# GateWay.net
KiCad netlist of a schematic drawn in Altium Designer
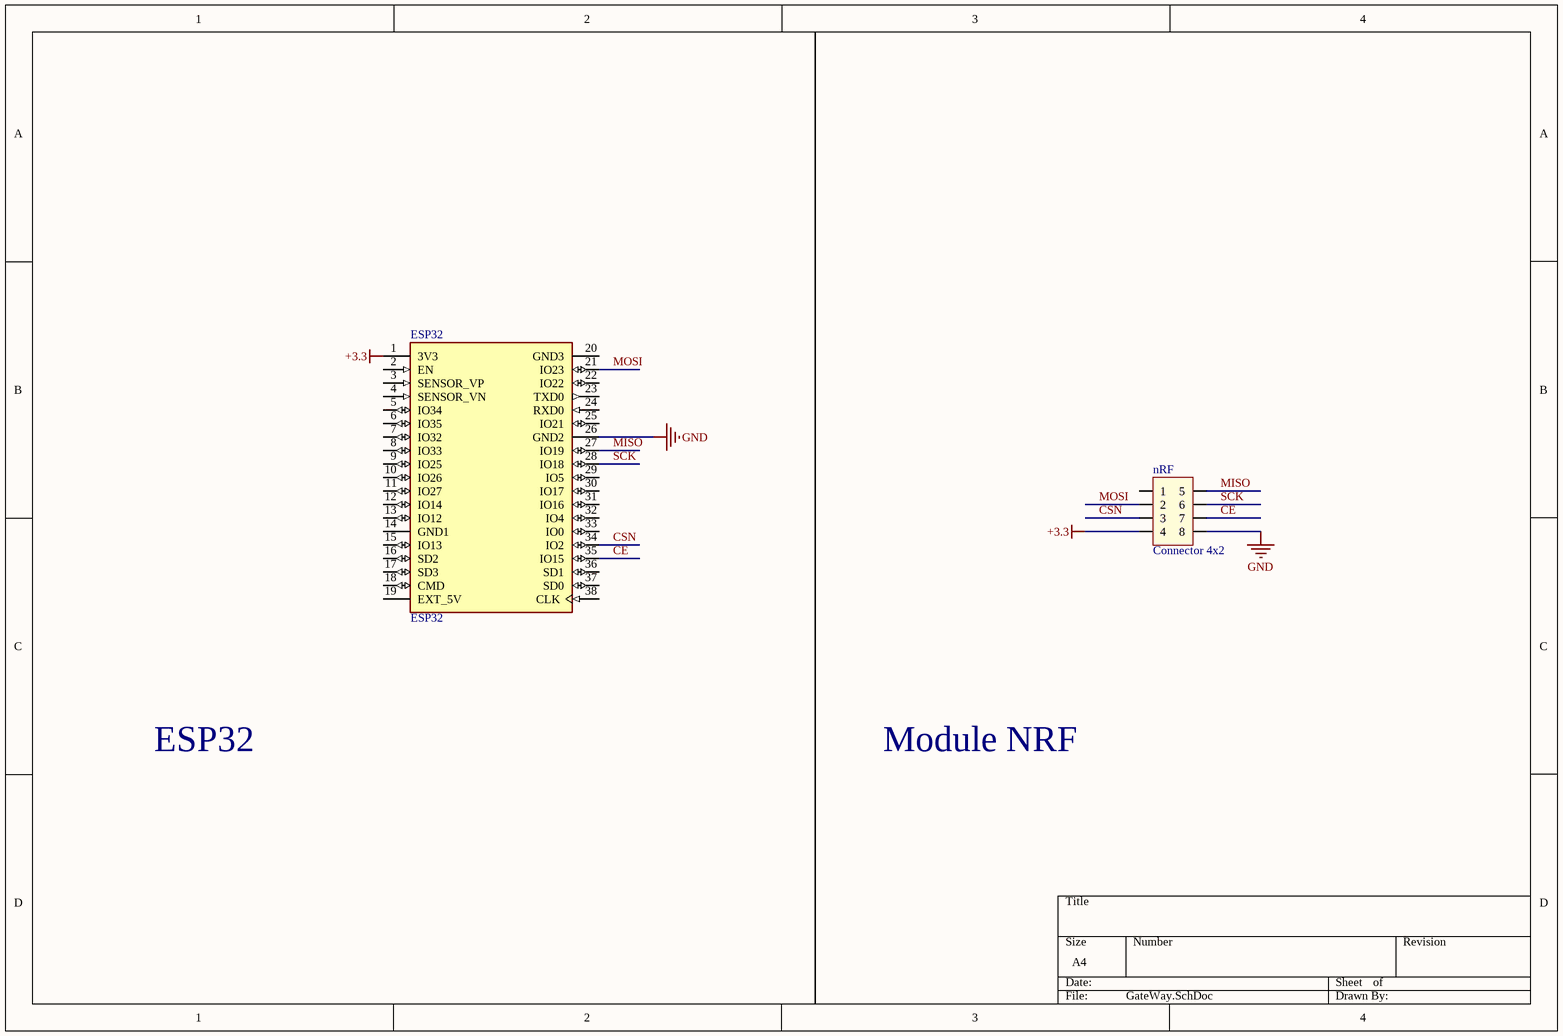
[diagram p0: GateWay.SchDoc]

(export (version "E")
  (design (tool "Eeschema 10.0.6"))
  (components
    (comp (ref "ESP32")
      (value "ESP32")
      (footprint "MODULE_ESP32-DEVKITC-32D")
      (description "EVAL BOARD FOR ESP-WROOM-32")
      (fields (field (name "MP") "ESP32-DEVKITC-32D") (field (name "MF") "Espressif Systems"))
      (libsource (lib "ESP32-DEVKITC-32D") (part "ESP32-DEVKITC-32D"))
    )
    (comp (ref "nRF")
      (value "Connector 4x2")
      (footprint "JP4x2")
      (libsource (lib "syhaunguyen__1") (part "JP4x2"))
    )
  )
  (nets
    (net (code "1") (name "+3.3") (class "Default")
      (node (ref "ESP32") (pin "1") (pinfunction "3V3_1") (pintype "power_in"))
      (node (ref "nRF") (pin "4") (pinfunction "4_4") (pintype "passive"))
    )
    (net (code "2") (name "/CE") (class "Default")
      (node (ref "ESP32") (pin "35") (pinfunction "IO15_35") (pintype "bidirectional"))
      (node (ref "nRF") (pin "7") (pinfunction "7_7") (pintype "passive"))
    )
    (net (code "3") (name "/CSN") (class "Default")
      (node (ref "ESP32") (pin "34") (pinfunction "IO2_34") (pintype "bidirectional"))
      (node (ref "nRF") (pin "3") (pinfunction "3_3") (pintype "passive"))
    )
    (net (code "4") (name "/MISO") (class "Default")
      (node (ref "ESP32") (pin "27") (pinfunction "IO19_27") (pintype "bidirectional"))
      (node (ref "nRF") (pin "5") (pinfunction "5_5") (pintype "passive"))
    )
    (net (code "5") (name "/MOSI") (class "Default")
      (node (ref "ESP32") (pin "21") (pinfunction "IO23_21") (pintype "bidirectional"))
      (node (ref "nRF") (pin "2") (pinfunction "2_2") (pintype "passive"))
    )
    (net (code "6") (name "/SCK") (class "Default")
      (node (ref "ESP32") (pin "28") (pinfunction "IO18_28") (pintype "bidirectional"))
      (node (ref "nRF") (pin "6") (pinfunction "6_6") (pintype "passive"))
    )
    (net (code "7") (name "GND") (class "Default")
      (node (ref "ESP32") (pin "26") (pinfunction "GND2_26") (pintype "power_in"))
      (node (ref "nRF") (pin "8") (pinfunction "8_8") (pintype "passive"))
    )
    (net (code "8") (name "unconnected-(ESP32-CLK-Pad38)") (class "Default")
      (node (ref "ESP32") (pin "38") (pinfunction "CLK_38") (pintype "input"))
    )
    (net (code "9") (name "unconnected-(ESP32-CMD-Pad18)") (class "Default")
      (node (ref "ESP32") (pin "18") (pinfunction "CMD_18") (pintype "bidirectional"))
    )
    (net (code "10") (name "unconnected-(ESP32-EN-Pad2)") (class "Default")
      (node (ref "ESP32") (pin "2") (pinfunction "EN_2") (pintype "input"))
    )
    (net (code "11") (name "unconnected-(ESP32-EXT_5V-Pad19)") (class "Default")
      (node (ref "ESP32") (pin "19") (pinfunction "EXT_5V_19") (pintype "power_in"))
    )
    (net (code "12") (name "unconnected-(ESP32-GND1-Pad14)") (class "Default")
      (node (ref "ESP32") (pin "14") (pinfunction "GND1_14") (pintype "power_in"))
    )
    (net (code "13") (name "unconnected-(ESP32-GND3-Pad20)") (class "Default")
      (node (ref "ESP32") (pin "20") (pinfunction "GND3_20") (pintype "power_in"))
    )
    (net (code "14") (name "unconnected-(ESP32-IO0-Pad33)") (class "Default")
      (node (ref "ESP32") (pin "33") (pinfunction "IO0_33") (pintype "bidirectional"))
    )
    (net (code "15") (name "unconnected-(ESP32-IO4-Pad32)") (class "Default")
      (node (ref "ESP32") (pin "32") (pinfunction "IO4_32") (pintype "bidirectional"))
    )
    (net (code "16") (name "unconnected-(ESP32-IO5-Pad29)") (class "Default")
      (node (ref "ESP32") (pin "29") (pinfunction "IO5_29") (pintype "bidirectional"))
    )
    (net (code "17") (name "unconnected-(ESP32-IO12-Pad13)") (class "Default")
      (node (ref "ESP32") (pin "13") (pinfunction "IO12_13") (pintype "bidirectional"))
    )
    (net (code "18") (name "unconnected-(ESP32-IO13-Pad15)") (class "Default")
      (node (ref "ESP32") (pin "15") (pinfunction "IO13_15") (pintype "bidirectional"))
    )
    (net (code "19") (name "unconnected-(ESP32-IO14-Pad12)") (class "Default")
      (node (ref "ESP32") (pin "12") (pinfunction "IO14_12") (pintype "bidirectional"))
    )
    (net (code "20") (name "unconnected-(ESP32-IO16-Pad31)") (class "Default")
      (node (ref "ESP32") (pin "31") (pinfunction "IO16_31") (pintype "bidirectional"))
    )
    (net (code "21") (name "unconnected-(ESP32-IO17-Pad30)") (class "Default")
      (node (ref "ESP32") (pin "30") (pinfunction "IO17_30") (pintype "bidirectional"))
    )
    (net (code "22") (name "unconnected-(ESP32-IO21-Pad25)") (class "Default")
      (node (ref "ESP32") (pin "25") (pinfunction "IO21_25") (pintype "bidirectional"))
    )
    (net (code "23") (name "unconnected-(ESP32-IO22-Pad22)") (class "Default")
      (node (ref "ESP32") (pin "22") (pinfunction "IO22_22") (pintype "bidirectional"))
    )
    (net (code "24") (name "unconnected-(ESP32-IO25-Pad9)") (class "Default")
      (node (ref "ESP32") (pin "9") (pinfunction "IO25_9") (pintype "bidirectional"))
    )
    (net (code "25") (name "unconnected-(ESP32-IO26-Pad10)") (class "Default")
      (node (ref "ESP32") (pin "10") (pinfunction "IO26_10") (pintype "bidirectional"))
    )
    (net (code "26") (name "unconnected-(ESP32-IO27-Pad11)") (class "Default")
      (node (ref "ESP32") (pin "11") (pinfunction "IO27_11") (pintype "bidirectional"))
    )
    (net (code "27") (name "unconnected-(ESP32-IO32-Pad7)") (class "Default")
      (node (ref "ESP32") (pin "7") (pinfunction "IO32_7") (pintype "bidirectional"))
    )
    (net (code "28") (name "unconnected-(ESP32-IO33-Pad8)") (class "Default")
      (node (ref "ESP32") (pin "8") (pinfunction "IO33_8") (pintype "bidirectional"))
    )
    (net (code "29") (name "unconnected-(ESP32-IO34-Pad5)") (class "Default")
      (node (ref "ESP32") (pin "5") (pinfunction "IO34_5") (pintype "bidirectional"))
    )
    (net (code "30") (name "unconnected-(ESP32-IO35-Pad6)") (class "Default")
      (node (ref "ESP32") (pin "6") (pinfunction "IO35_6") (pintype "bidirectional"))
    )
    (net (code "31") (name "unconnected-(ESP32-RXD0-Pad24)") (class "Default")
      (node (ref "ESP32") (pin "24") (pinfunction "RXD0_24") (pintype "input"))
    )
    (net (code "32") (name "unconnected-(ESP32-SD0-Pad37)") (class "Default")
      (node (ref "ESP32") (pin "37") (pinfunction "SD0_37") (pintype "bidirectional"))
    )
    (net (code "33") (name "unconnected-(ESP32-SD1-Pad36)") (class "Default")
      (node (ref "ESP32") (pin "36") (pinfunction "SD1_36") (pintype "bidirectional"))
    )
    (net (code "34") (name "unconnected-(ESP32-SD2-Pad16)") (class "Default")
      (node (ref "ESP32") (pin "16") (pinfunction "SD2_16") (pintype "bidirectional"))
    )
    (net (code "35") (name "unconnected-(ESP32-SD3-Pad17)") (class "Default")
      (node (ref "ESP32") (pin "17") (pinfunction "SD3_17") (pintype "bidirectional"))
    )
    (net (code "36") (name "unconnected-(ESP32-SENSOR_VN-Pad4)") (class "Default")
      (node (ref "ESP32") (pin "4") (pinfunction "SENSOR_VN_4") (pintype "input"))
    )
    (net (code "37") (name "unconnected-(ESP32-SENSOR_VP-Pad3)") (class "Default")
      (node (ref "ESP32") (pin "3") (pinfunction "SENSOR_VP_3") (pintype "input"))
    )
    (net (code "38") (name "unconnected-(ESP32-TXD0-Pad23)") (class "Default")
      (node (ref "ESP32") (pin "23") (pinfunction "TXD0_23") (pintype "output"))
    )
    (net (code "39") (name "unconnected-(nRF-Pad1)") (class "Default")
      (node (ref "nRF") (pin "1") (pinfunction "1_1") (pintype "passive"))
    )
  )
)
